# Arduino_Clock_Dividerx4_board1_reduced_t.net
KiCad netlist of a schematic drawn in EAGLE
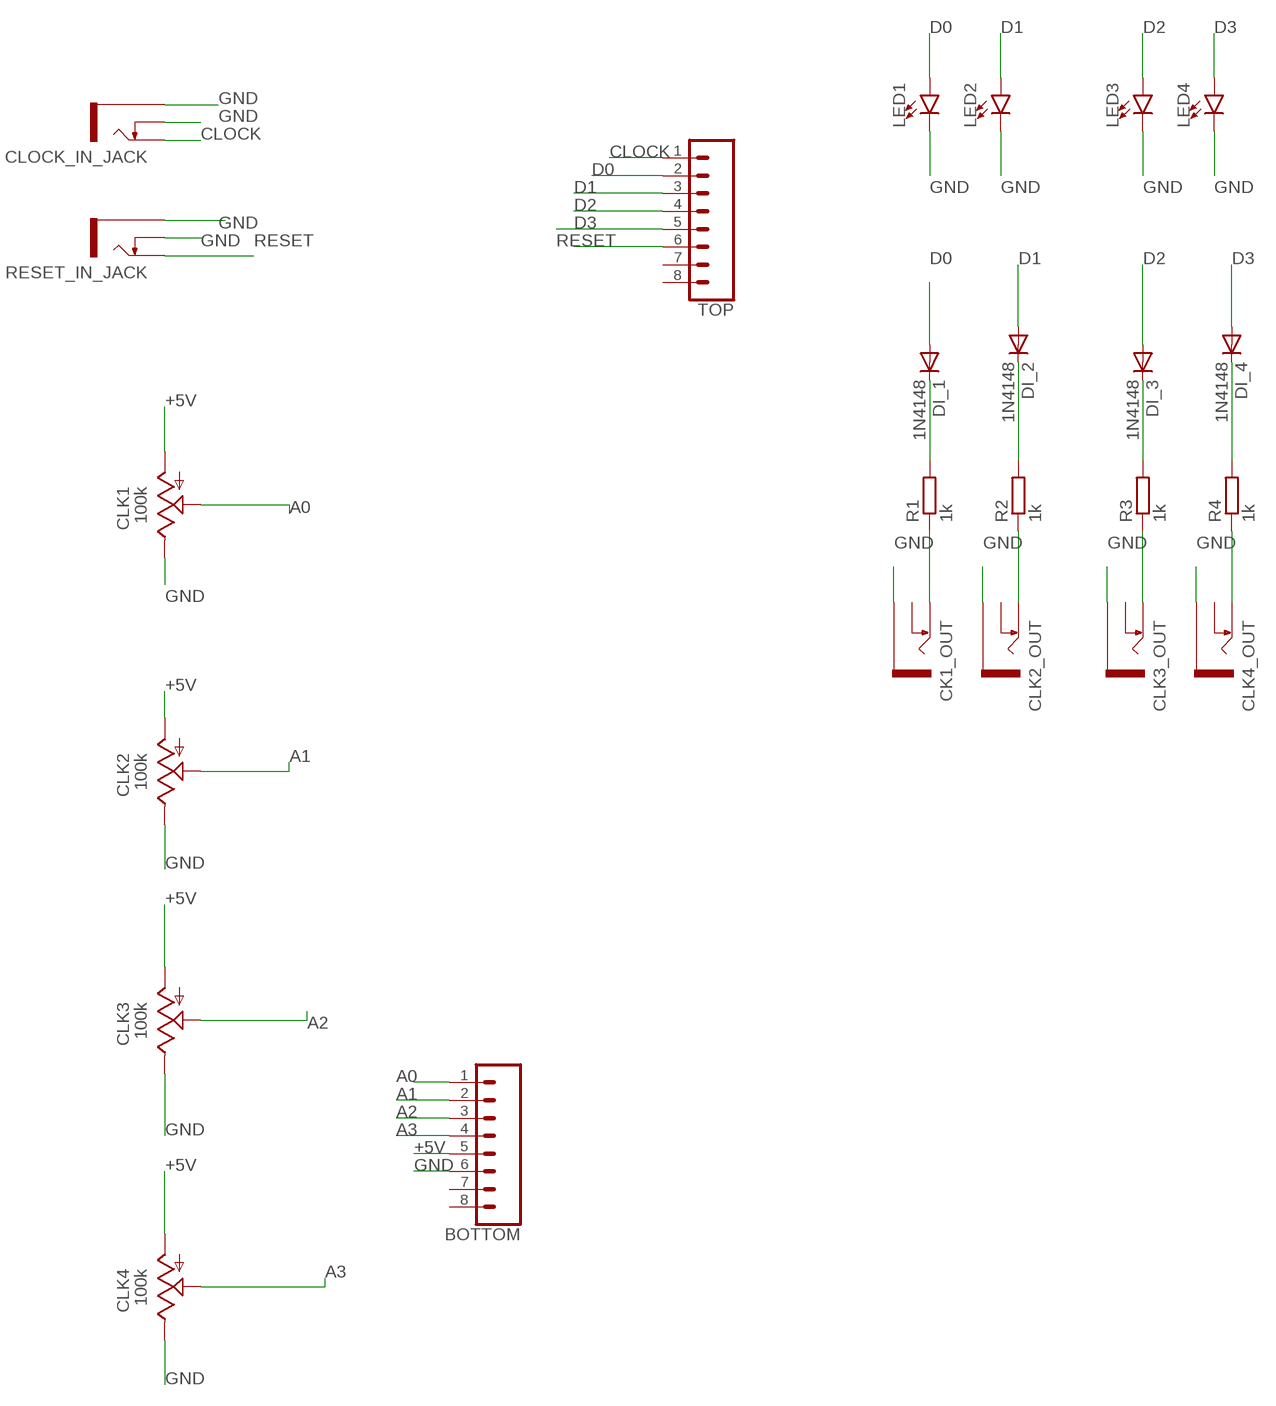
[diagram p0: schematic, sheet 1]

(export (version "E")
  (design (tool "Eeschema 10.0.6"))
  (components
    (comp (ref "BOTTOM")
      (value "CONN_08LONGPADS")
      (footprint "eagle-import:1X08_LONGPADS")
      (libsource (lib "eagle-import") (part "CONN_08LONGPADS"))
    )
    (comp (ref "CK1_OUT")
      (value "THONKICONNNEW")
      (footprint "eagle-import:WQP-PJ301M-12_JACK")
      (libsource (lib "eagle-import") (part "THONKICONNNEW"))
    )
    (comp (ref "CLK1")
      (value "100k")
      (footprint "eagle-import:9MM_SNAP-IN_POT")
      (libsource (lib "eagle-import") (part "9MM_SNAP-IN_POT_"))
    )
    (comp (ref "CLK2")
      (value "100k")
      (footprint "eagle-import:9MM_SNAP-IN_POT")
      (libsource (lib "eagle-import") (part "9MM_SNAP-IN_POT_"))
    )
    (comp (ref "CLK2_OUT")
      (value "THONKICONNNEW")
      (footprint "eagle-import:WQP-PJ301M-12_JACK")
      (libsource (lib "eagle-import") (part "THONKICONNNEW"))
    )
    (comp (ref "CLK3")
      (value "100k")
      (footprint "eagle-import:9MM_SNAP-IN_POT")
      (libsource (lib "eagle-import") (part "9MM_SNAP-IN_POT_"))
    )
    (comp (ref "CLK3_OUT")
      (value "THONKICONNNEW")
      (footprint "eagle-import:WQP-PJ301M-12_JACK")
      (libsource (lib "eagle-import") (part "THONKICONNNEW"))
    )
    (comp (ref "CLK4")
      (value "100k")
      (footprint "eagle-import:9MM_SNAP-IN_POT")
      (libsource (lib "eagle-import") (part "9MM_SNAP-IN_POT_"))
    )
    (comp (ref "CLK4_OUT")
      (value "THONKICONNNEW")
      (footprint "eagle-import:WQP-PJ301M-12_JACK")
      (libsource (lib "eagle-import") (part "THONKICONNNEW"))
    )
    (comp (ref "CLOCK_IN_JACK")
      (value "THONKICONNNEW")
      (footprint "eagle-import:WQP-PJ301M-12_JACK")
      (libsource (lib "eagle-import") (part "THONKICONNNEW"))
    )
    (comp (ref "DI_1")
      (value "1N4148")
      (footprint "eagle-import:DO35-7")
      (libsource (lib "eagle-import") (part "SMALL_DIODEDO35-7"))
    )
    (comp (ref "DI_2")
      (value "1N4148")
      (footprint "eagle-import:DO35-7")
      (libsource (lib "eagle-import") (part "SMALL_DIODEDO35-7"))
    )
    (comp (ref "DI_3")
      (value "1N4148")
      (footprint "eagle-import:DO35-7")
      (libsource (lib "eagle-import") (part "SMALL_DIODEDO35-7"))
    )
    (comp (ref "DI_4")
      (value "1N4148")
      (footprint "eagle-import:DO35-7")
      (libsource (lib "eagle-import") (part "SMALL_DIODEDO35-7"))
    )
    (comp (ref "LED1")
      (value "LED3MM")
      (footprint "eagle-import:LED_3MM")
      (fields (field (name "SPICEPREFIX") "L"))
      (libsource (lib "eagle-import") (part "LED3MM"))
    )
    (comp (ref "LED2")
      (value "LED3MM")
      (footprint "eagle-import:LED_3MM")
      (fields (field (name "SPICEPREFIX") "L"))
      (libsource (lib "eagle-import") (part "LED3MM"))
    )
    (comp (ref "LED3")
      (value "LED3MM")
      (footprint "eagle-import:LED_3MM")
      (fields (field (name "SPICEPREFIX") "L"))
      (libsource (lib "eagle-import") (part "LED3MM"))
    )
    (comp (ref "LED4")
      (value "LED3MM")
      (footprint "eagle-import:LED_3MM")
      (fields (field (name "SPICEPREFIX") "L"))
      (libsource (lib "eagle-import") (part "LED3MM"))
    )
    (comp (ref "R1")
      (value "1k")
      (footprint "eagle-import:7MM_RESISTOR")
      (libsource (lib "eagle-import") (part "RESISTOR7MM"))
    )
    (comp (ref "R2")
      (value "1k")
      (footprint "eagle-import:7MM_RESISTOR")
      (libsource (lib "eagle-import") (part "RESISTOR7MM"))
    )
    (comp (ref "R3")
      (value "1k")
      (footprint "eagle-import:7MM_RESISTOR")
      (libsource (lib "eagle-import") (part "RESISTOR7MM"))
    )
    (comp (ref "R4")
      (value "1k")
      (footprint "eagle-import:7MM_RESISTOR")
      (libsource (lib "eagle-import") (part "RESISTOR7MM"))
    )
    (comp (ref "RESET_IN_JACK")
      (value "THONKICONNNEW")
      (footprint "eagle-import:WQP-PJ301M-12_JACK")
      (libsource (lib "eagle-import") (part "THONKICONNNEW"))
    )
    (comp (ref "TOP")
      (value "CONN_08LONGPADS")
      (footprint "eagle-import:1X08_LONGPADS")
      (libsource (lib "eagle-import") (part "CONN_08LONGPADS"))
    )
  )
  (nets
    (net (code "1") (name "/+5V") (class "Default")
      (node (ref "BOTTOM") (pin "5") (pinfunction "5_5") (pintype "passive"))
      (node (ref "CLK1") (pin "1") (pinfunction "A_1") (pintype "passive"))
      (node (ref "CLK2") (pin "1") (pinfunction "A_1") (pintype "passive"))
      (node (ref "CLK3") (pin "1") (pinfunction "A_1") (pintype "passive"))
      (node (ref "CLK4") (pin "1") (pinfunction "A_1") (pintype "passive"))
    )
    (net (code "2") (name "/A0") (class "Default")
      (node (ref "BOTTOM") (pin "1") (pinfunction "1_1") (pintype "passive"))
      (node (ref "CLK1") (pin "2") (pinfunction "S_2") (pintype "passive"))
    )
    (net (code "3") (name "/A1") (class "Default")
      (node (ref "BOTTOM") (pin "2") (pinfunction "2_2") (pintype "passive"))
      (node (ref "CLK2") (pin "2") (pinfunction "S_2") (pintype "passive"))
    )
    (net (code "4") (name "/A2") (class "Default")
      (node (ref "BOTTOM") (pin "3") (pinfunction "3_3") (pintype "passive"))
      (node (ref "CLK3") (pin "2") (pinfunction "S_2") (pintype "passive"))
    )
    (net (code "5") (name "/A3") (class "Default")
      (node (ref "BOTTOM") (pin "4") (pinfunction "4_4") (pintype "passive"))
      (node (ref "CLK4") (pin "2") (pinfunction "S_2") (pintype "passive"))
    )
    (net (code "6") (name "/CLOCK") (class "Default")
      (node (ref "CLOCK_IN_JACK") (pin "P$1_TIP") (pinfunction "TIP_P$1_TIP") (pintype "passive"))
      (node (ref "TOP") (pin "1") (pinfunction "1_1") (pintype "passive"))
    )
    (net (code "7") (name "/D0") (class "Default")
      (node (ref "DI_1") (pin "A") (pinfunction "A_A") (pintype "passive"))
      (node (ref "LED1") (pin "A") (pinfunction "A_A") (pintype "passive"))
      (node (ref "TOP") (pin "2") (pinfunction "2_2") (pintype "passive"))
    )
    (net (code "8") (name "/D1") (class "Default")
      (node (ref "DI_2") (pin "A") (pinfunction "A_A") (pintype "passive"))
      (node (ref "LED2") (pin "A") (pinfunction "A_A") (pintype "passive"))
      (node (ref "TOP") (pin "3") (pinfunction "3_3") (pintype "passive"))
    )
    (net (code "9") (name "/D2") (class "Default")
      (node (ref "DI_3") (pin "A") (pinfunction "A_A") (pintype "passive"))
      (node (ref "LED3") (pin "A") (pinfunction "A_A") (pintype "passive"))
      (node (ref "TOP") (pin "4") (pinfunction "4_4") (pintype "passive"))
    )
    (net (code "10") (name "/D3") (class "Default")
      (node (ref "DI_4") (pin "A") (pinfunction "A_A") (pintype "passive"))
      (node (ref "LED4") (pin "A") (pinfunction "A_A") (pintype "passive"))
      (node (ref "TOP") (pin "5") (pinfunction "5_5") (pintype "passive"))
    )
    (net (code "11") (name "/GND") (class "Default")
      (node (ref "BOTTOM") (pin "6") (pinfunction "6_6") (pintype "passive"))
      (node (ref "CK1_OUT") (pin "P$3_SLEEVE") (pinfunction "SLEEVE_P$3_SLEEVE") (pintype "passive"))
      (node (ref "CLK1") (pin "3") (pinfunction "E_3") (pintype "passive"))
      (node (ref "CLK2") (pin "3") (pinfunction "E_3") (pintype "passive"))
      (node (ref "CLK2_OUT") (pin "P$3_SLEEVE") (pinfunction "SLEEVE_P$3_SLEEVE") (pintype "passive"))
      (node (ref "CLK3") (pin "3") (pinfunction "E_3") (pintype "passive"))
      (node (ref "CLK3_OUT") (pin "P$3_SLEEVE") (pinfunction "SLEEVE_P$3_SLEEVE") (pintype "passive"))
      (node (ref "CLK4") (pin "3") (pinfunction "E_3") (pintype "passive"))
      (node (ref "CLK4_OUT") (pin "P$3_SLEEVE") (pinfunction "SLEEVE_P$3_SLEEVE") (pintype "passive"))
      (node (ref "CLOCK_IN_JACK") (pin "P$2_SWITCH") (pinfunction "SWITCH_P$2_SWITCH") (pintype "passive"))
      (node (ref "CLOCK_IN_JACK") (pin "P$3_SLEEVE") (pinfunction "SLEEVE_P$3_SLEEVE") (pintype "passive"))
      (node (ref "LED1") (pin "K") (pinfunction "C_K") (pintype "passive"))
      (node (ref "LED2") (pin "K") (pinfunction "C_K") (pintype "passive"))
      (node (ref "LED3") (pin "K") (pinfunction "C_K") (pintype "passive"))
      (node (ref "LED4") (pin "K") (pinfunction "C_K") (pintype "passive"))
      (node (ref "RESET_IN_JACK") (pin "P$2_SWITCH") (pinfunction "SWITCH_P$2_SWITCH") (pintype "passive"))
      (node (ref "RESET_IN_JACK") (pin "P$3_SLEEVE") (pinfunction "SLEEVE_P$3_SLEEVE") (pintype "passive"))
    )
    (net (code "12") (name "/RESET") (class "Default")
      (node (ref "RESET_IN_JACK") (pin "P$1_TIP") (pinfunction "TIP_P$1_TIP") (pintype "passive"))
      (node (ref "TOP") (pin "6") (pinfunction "6_6") (pintype "passive"))
    )
    (net (code "13") (name "Net-(CK1_OUT-TIP)") (class "Default")
      (node (ref "CK1_OUT") (pin "P$1_TIP") (pinfunction "TIP_P$1_TIP") (pintype "passive"))
      (node (ref "R1") (pin "1") (pinfunction "1_1") (pintype "passive"))
    )
    (net (code "14") (name "Net-(CLK2_OUT-TIP)") (class "Default")
      (node (ref "CLK2_OUT") (pin "P$1_TIP") (pinfunction "TIP_P$1_TIP") (pintype "passive"))
      (node (ref "R2") (pin "1") (pinfunction "1_1") (pintype "passive"))
    )
    (net (code "15") (name "Net-(CLK3_OUT-TIP)") (class "Default")
      (node (ref "CLK3_OUT") (pin "P$1_TIP") (pinfunction "TIP_P$1_TIP") (pintype "passive"))
      (node (ref "R3") (pin "1") (pinfunction "1_1") (pintype "passive"))
    )
    (net (code "16") (name "Net-(CLK4_OUT-TIP)") (class "Default")
      (node (ref "CLK4_OUT") (pin "P$1_TIP") (pinfunction "TIP_P$1_TIP") (pintype "passive"))
      (node (ref "R4") (pin "1") (pinfunction "1_1") (pintype "passive"))
    )
    (net (code "17") (name "Net-(DI_1-PadC)") (class "Default")
      (node (ref "DI_1") (pin "C") (pinfunction "C_C") (pintype "passive"))
      (node (ref "R1") (pin "2") (pinfunction "2_2") (pintype "passive"))
    )
    (net (code "18") (name "Net-(DI_2-PadC)") (class "Default")
      (node (ref "DI_2") (pin "C") (pinfunction "C_C") (pintype "passive"))
      (node (ref "R2") (pin "2") (pinfunction "2_2") (pintype "passive"))
    )
    (net (code "19") (name "Net-(DI_3-PadC)") (class "Default")
      (node (ref "DI_3") (pin "C") (pinfunction "C_C") (pintype "passive"))
      (node (ref "R3") (pin "2") (pinfunction "2_2") (pintype "passive"))
    )
    (net (code "20") (name "Net-(DI_4-PadC)") (class "Default")
      (node (ref "DI_4") (pin "C") (pinfunction "C_C") (pintype "passive"))
      (node (ref "R4") (pin "2") (pinfunction "2_2") (pintype "passive"))
    )
    (net (code "21") (name "unconnected-(BOTTOM-Pad7)") (class "Default")
      (node (ref "BOTTOM") (pin "7") (pinfunction "7_7") (pintype "passive"))
    )
    (net (code "22") (name "unconnected-(BOTTOM-Pad8)") (class "Default")
      (node (ref "BOTTOM") (pin "8") (pinfunction "8_8") (pintype "passive"))
    )
    (net (code "23") (name "unconnected-(CK1_OUT-SWITCH-PadP$2_SWITCH)") (class "Default")
      (node (ref "CK1_OUT") (pin "P$2_SWITCH") (pinfunction "SWITCH_P$2_SWITCH") (pintype "passive"))
    )
    (net (code "24") (name "unconnected-(CLK2_OUT-SWITCH-PadP$2_SWITCH)") (class "Default")
      (node (ref "CLK2_OUT") (pin "P$2_SWITCH") (pinfunction "SWITCH_P$2_SWITCH") (pintype "passive"))
    )
    (net (code "25") (name "unconnected-(CLK3_OUT-SWITCH-PadP$2_SWITCH)") (class "Default")
      (node (ref "CLK3_OUT") (pin "P$2_SWITCH") (pinfunction "SWITCH_P$2_SWITCH") (pintype "passive"))
    )
    (net (code "26") (name "unconnected-(CLK4_OUT-SWITCH-PadP$2_SWITCH)") (class "Default")
      (node (ref "CLK4_OUT") (pin "P$2_SWITCH") (pinfunction "SWITCH_P$2_SWITCH") (pintype "passive"))
    )
    (net (code "27") (name "unconnected-(TOP-Pad7)") (class "Default")
      (node (ref "TOP") (pin "7") (pinfunction "7_7") (pintype "passive"))
    )
    (net (code "28") (name "unconnected-(TOP-Pad8)") (class "Default")
      (node (ref "TOP") (pin "8") (pinfunction "8_8") (pintype "passive"))
    )
  )
)
